# chamberbiasa.net
KiCad netlist of a schematic drawn in EAGLE
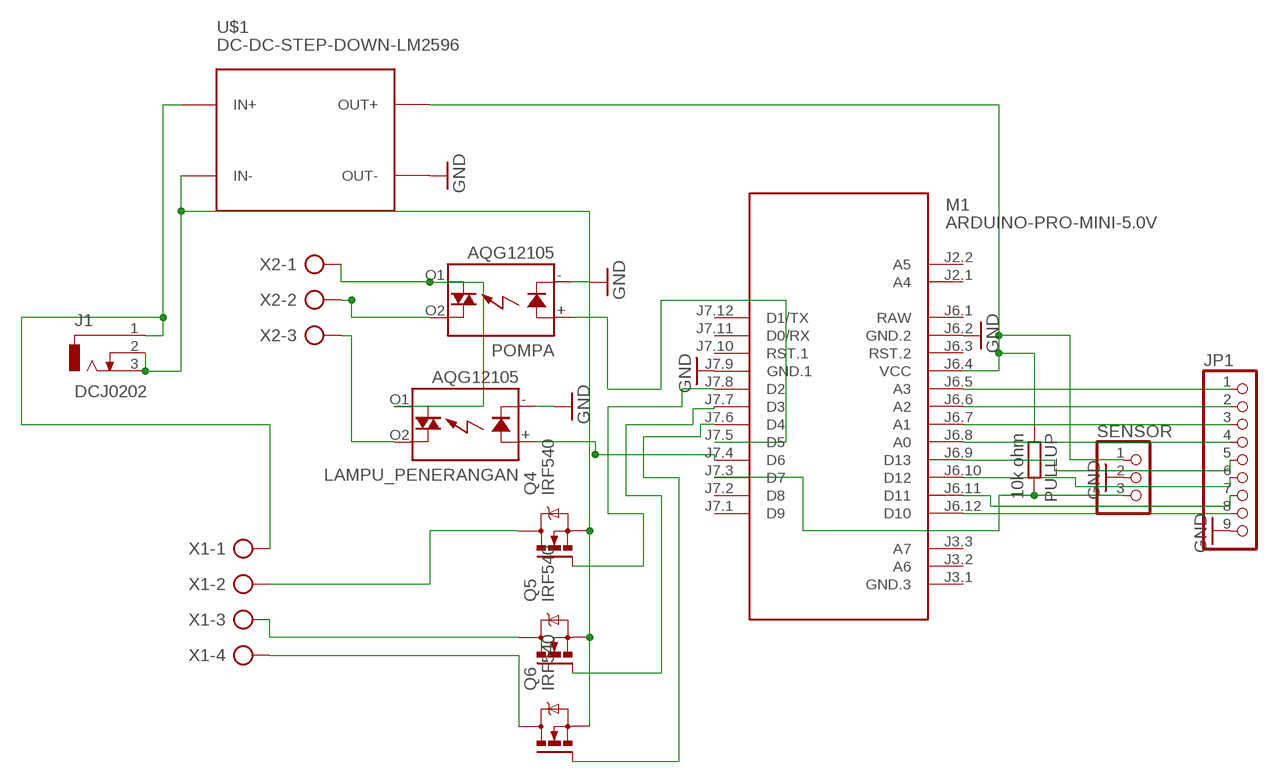
[diagram p0: schematic, sheet 1]

(export (version "E")
  (design (tool "Eeschema 10.0.6"))
  (components
    (comp (ref "J1")
      (value "DCJ0202")
      (footprint "eagle-import:DCJ0202")
      (libsource (lib "eagle-import") (part "DCJ0202"))
    )
    (comp (ref "JP1")
      (value "PINHD-1X9")
      (footprint "eagle-import:1X09")
      (libsource (lib "eagle-import") (part "PINHD-1X9"))
    )
    (comp (ref "LAMPU_PENERANGAN")
      (value "AQG12105")
      (footprint "eagle-import:AQG")
      (fields (field (name "MF") "AROMAT/ MATSUSHITA"))
      (libsource (lib "eagle-import") (part "AQG12105"))
    )
    (comp (ref "M1")
      (value "ARDUINO-PRO-MINI-5.0V")
      (footprint "eagle-import:ARDUINO-PRO-MINI")
      (libsource (lib "eagle-import") (part "ARDUINO-PRO-MINI-5.0V"))
    )
    (comp (ref "POMPA")
      (value "AQG12105")
      (footprint "eagle-import:AQG")
      (fields (field (name "MF") "AROMAT/ MATSUSHITA"))
      (libsource (lib "eagle-import") (part "AQG12105"))
    )
    (comp (ref "PULLUP")
      (value "10k ohm")
      (footprint "eagle-import:0204_7")
      (libsource (lib "eagle-import") (part "R-EU_0204/7"))
    )
    (comp (ref "Q4")
      (value "IRF540")
      (footprint "eagle-import:TO220BV")
      (libsource (lib "eagle-import") (part "IRF540"))
    )
    (comp (ref "Q5")
      (value "IRF540")
      (footprint "eagle-import:TO220BV")
      (libsource (lib "eagle-import") (part "IRF540"))
    )
    (comp (ref "Q6")
      (value "IRF540")
      (footprint "eagle-import:TO220BV")
      (libsource (lib "eagle-import") (part "IRF540"))
    )
    (comp (ref "SENSOR")
      (value "PINHD-1X3")
      (footprint "eagle-import:1X03")
      (libsource (lib "eagle-import") (part "PINHD-1X3"))
    )
    (comp (ref "U$1")
      (value "DC-DC-STEP-DOWN-LM2596")
      (footprint "eagle-import:DC-DC-STEP-DOWN-LM2596")
      (libsource (lib "eagle-import") (part "DC-DC-STEP-DOWN-LM2596"))
    )
    (comp (ref "X1")
      (value "AK300/4")
      (footprint "eagle-import:AK300_4")
      (libsource (lib "eagle-import") (part "AK300/4"))
    )
    (comp (ref "X2")
      (value "AK300/3")
      (footprint "eagle-import:AK300_3")
      (libsource (lib "eagle-import") (part "AK300/3"))
    )
  )
  (nets
    (net (code "1") (name "/RAW") (class "Default")
      (node (ref "M1") (pin "J6.1") (pinfunction "RAW_J6.1") (pintype "power_in"))
    )
    (net (code "2") (name "GND") (class "Default")
      (node (ref "JP1") (pin "9") (pinfunction "9_9") (pintype "passive"))
      (node (ref "LAMPU_PENERANGAN") (pin "-") (pinfunction "K_-") (pintype "passive"))
      (node (ref "M1") (pin "J6.2") (pinfunction "GND.2_J6.2") (pintype "power_in"))
      (node (ref "M1") (pin "J7.9") (pinfunction "GND.1_J7.9") (pintype "power_in"))
      (node (ref "POMPA") (pin "-") (pinfunction "K_-") (pintype "passive"))
      (node (ref "SENSOR") (pin "2") (pinfunction "2_2") (pintype "passive"))
      (node (ref "U$1") (pin "OUT-") (pinfunction "OUT-_OUT-") (pintype "bidirectional"))
    )
    (net (code "3") (name "Net-(J1-Pad2)") (class "Default")
      (node (ref "J1") (pin "2") (pinfunction "2_2") (pintype "passive"))
      (node (ref "J1") (pin "3") (pinfunction "3_3") (pintype "passive"))
      (node (ref "Q4") (pin "S") (pinfunction "S_S") (pintype "passive"))
      (node (ref "Q5") (pin "S") (pinfunction "S_S") (pintype "passive"))
      (node (ref "Q6") (pin "S") (pinfunction "S_S") (pintype "passive"))
      (node (ref "U$1") (pin "IN-") (pinfunction "IN-_IN-") (pintype "bidirectional"))
    )
    (net (code "4") (name "Net-(LAMPU_PENERANGAN-A)") (class "Default")
      (node (ref "LAMPU_PENERANGAN") (pin "+") (pinfunction "A_+") (pintype "passive"))
      (node (ref "M1") (pin "J7.4") (pinfunction "D6_J7.4") (pintype "bidirectional"))
    )
    (net (code "5") (name "Net-(LAMPU_PENERANGAN-DS1)") (class "Default")
      (node (ref "LAMPU_PENERANGAN") (pin "O2") (pinfunction "DS1_O2") (pintype "passive"))
      (node (ref "X2") (pin "3") (pinfunction "KL_3") (pintype "passive"))
    )
    (net (code "6") (name "Net-(LAMPU_PENERANGAN-DS2)") (class "Default")
      (node (ref "LAMPU_PENERANGAN") (pin "O1") (pinfunction "DS2_O1") (pintype "passive"))
      (node (ref "POMPA") (pin "O1") (pinfunction "DS2_O1") (pintype "passive"))
      (node (ref "X2") (pin "1") (pinfunction "KL_1") (pintype "passive"))
    )
    (net (code "7") (name "Net-(M1-A0)") (class "Default")
      (node (ref "JP1") (pin "4") (pinfunction "4_4") (pintype "passive"))
      (node (ref "M1") (pin "J6.8") (pinfunction "A0_J6.8") (pintype "bidirectional"))
    )
    (net (code "8") (name "Net-(M1-A1)") (class "Default")
      (node (ref "JP1") (pin "3") (pinfunction "3_3") (pintype "passive"))
      (node (ref "M1") (pin "J6.7") (pinfunction "A1_J6.7") (pintype "bidirectional"))
    )
    (net (code "9") (name "Net-(M1-A2)") (class "Default")
      (node (ref "JP1") (pin "2") (pinfunction "2_2") (pintype "passive"))
      (node (ref "M1") (pin "J6.6") (pinfunction "A2_J6.6") (pintype "bidirectional"))
    )
    (net (code "10") (name "Net-(M1-A3)") (class "Default")
      (node (ref "JP1") (pin "1") (pinfunction "1_1") (pintype "passive"))
      (node (ref "M1") (pin "J6.5") (pinfunction "A3_J6.5") (pintype "bidirectional"))
    )
    (net (code "11") (name "Net-(M1-D2)") (class "Default")
      (node (ref "M1") (pin "J7.8") (pinfunction "D2_J7.8") (pintype "bidirectional"))
      (node (ref "Q4") (pin "G") (pinfunction "G_G") (pintype "passive"))
    )
    (net (code "12") (name "Net-(M1-D3)") (class "Default")
      (node (ref "M1") (pin "J7.7") (pinfunction "D3_J7.7") (pintype "bidirectional"))
      (node (ref "Q5") (pin "G") (pinfunction "G_G") (pintype "passive"))
    )
    (net (code "13") (name "Net-(M1-D4)") (class "Default")
      (node (ref "M1") (pin "J7.6") (pinfunction "D4_J7.6") (pintype "bidirectional"))
      (node (ref "Q6") (pin "G") (pinfunction "G_G") (pintype "passive"))
    )
    (net (code "14") (name "Net-(M1-D5)") (class "Default")
      (node (ref "M1") (pin "J7.5") (pinfunction "D5_J7.5") (pintype "bidirectional"))
      (node (ref "POMPA") (pin "+") (pinfunction "A_+") (pintype "passive"))
    )
    (net (code "15") (name "Net-(M1-D7)") (class "Default")
      (node (ref "M1") (pin "J7.3") (pinfunction "D7_J7.3") (pintype "bidirectional"))
      (node (ref "PULLUP") (pin "2") (pinfunction "2_2") (pintype "passive"))
      (node (ref "SENSOR") (pin "3") (pinfunction "3_3") (pintype "passive"))
    )
    (net (code "16") (name "Net-(M1-D10)") (class "Default")
      (node (ref "JP1") (pin "8") (pinfunction "8_8") (pintype "passive"))
      (node (ref "M1") (pin "J6.12") (pinfunction "D10_J6.12") (pintype "bidirectional"))
    )
    (net (code "17") (name "Net-(M1-D11)") (class "Default")
      (node (ref "JP1") (pin "7") (pinfunction "7_7") (pintype "passive"))
      (node (ref "M1") (pin "J6.11") (pinfunction "D11_J6.11") (pintype "bidirectional"))
    )
    (net (code "18") (name "Net-(M1-D12)") (class "Default")
      (node (ref "JP1") (pin "6") (pinfunction "6_6") (pintype "passive"))
      (node (ref "M1") (pin "J6.10") (pinfunction "D12_J6.10") (pintype "bidirectional"))
    )
    (net (code "19") (name "Net-(M1-D13)") (class "Default")
      (node (ref "JP1") (pin "5") (pinfunction "5_5") (pintype "passive"))
      (node (ref "M1") (pin "J6.9") (pinfunction "D13_J6.9") (pintype "bidirectional"))
    )
    (net (code "20") (name "Net-(M1-VCC)") (class "Default")
      (node (ref "M1") (pin "J6.4") (pinfunction "VCC_J6.4") (pintype "power_in"))
      (node (ref "PULLUP") (pin "1") (pinfunction "1_1") (pintype "passive"))
      (node (ref "SENSOR") (pin "1") (pinfunction "1_1") (pintype "passive"))
      (node (ref "U$1") (pin "OUT+") (pinfunction "OUT+_OUT+") (pintype "bidirectional"))
    )
    (net (code "21") (name "Net-(POMPA-DS1)") (class "Default")
      (node (ref "POMPA") (pin "O2") (pinfunction "DS1_O2") (pintype "passive"))
      (node (ref "X2") (pin "2") (pinfunction "KL_2") (pintype "passive"))
    )
    (net (code "22") (name "Net-(X1A-KL)") (class "Default")
      (node (ref "J1") (pin "1") (pinfunction "1_1") (pintype "passive"))
      (node (ref "U$1") (pin "IN+") (pinfunction "IN+_IN+") (pintype "bidirectional"))
      (node (ref "X1") (pin "1") (pinfunction "KL_1") (pintype "passive"))
    )
    (net (code "23") (name "Net-(X1B-KL)") (class "Default")
      (node (ref "Q4") (pin "D") (pinfunction "D_D") (pintype "passive"))
      (node (ref "X1") (pin "2") (pinfunction "KL_2") (pintype "passive"))
    )
    (net (code "24") (name "Net-(X1C-KL)") (class "Default")
      (node (ref "Q5") (pin "D") (pinfunction "D_D") (pintype "passive"))
      (node (ref "X1") (pin "3") (pinfunction "KL_3") (pintype "passive"))
    )
    (net (code "25") (name "Net-(X1D-KL)") (class "Default")
      (node (ref "Q6") (pin "D") (pinfunction "D_D") (pintype "passive"))
      (node (ref "X1") (pin "4") (pinfunction "KL_4") (pintype "passive"))
    )
    (net (code "26") (name "unconnected-(M1-A4-PadJ2.1)") (class "Default")
      (node (ref "M1") (pin "J2.1") (pinfunction "A4_J2.1") (pintype "bidirectional"))
    )
    (net (code "27") (name "unconnected-(M1-A5-PadJ2.2)") (class "Default")
      (node (ref "M1") (pin "J2.2") (pinfunction "A5_J2.2") (pintype "bidirectional"))
    )
    (net (code "28") (name "unconnected-(M1-A6-PadJ3.2)") (class "Default")
      (node (ref "M1") (pin "J3.2") (pinfunction "A6_J3.2") (pintype "bidirectional"))
    )
    (net (code "29") (name "unconnected-(M1-A7-PadJ3.3)") (class "Default")
      (node (ref "M1") (pin "J3.3") (pinfunction "A7_J3.3") (pintype "bidirectional"))
    )
    (net (code "30") (name "unconnected-(M1-D0{slash}RX-PadJ7.11)") (class "Default")
      (node (ref "M1") (pin "J7.11") (pinfunction "D0/RX_J7.11") (pintype "bidirectional"))
    )
    (net (code "31") (name "unconnected-(M1-D1{slash}TX-PadJ7.12)") (class "Default")
      (node (ref "M1") (pin "J7.12") (pinfunction "D1/TX_J7.12") (pintype "bidirectional"))
    )
    (net (code "32") (name "unconnected-(M1-D8-PadJ7.2)") (class "Default")
      (node (ref "M1") (pin "J7.2") (pinfunction "D8_J7.2") (pintype "bidirectional"))
    )
    (net (code "33") (name "unconnected-(M1-D9-PadJ7.1)") (class "Default")
      (node (ref "M1") (pin "J7.1") (pinfunction "D9_J7.1") (pintype "bidirectional"))
    )
    (net (code "34") (name "unconnected-(M1-GND.3-PadJ3.1)") (class "Default")
      (node (ref "M1") (pin "J3.1") (pinfunction "GND.3_J3.1") (pintype "bidirectional"))
    )
    (net (code "35") (name "unconnected-(M1-RST.1-PadJ7.10)") (class "Default")
      (node (ref "M1") (pin "J7.10") (pinfunction "RST.1_J7.10") (pintype "bidirectional"))
    )
    (net (code "36") (name "unconnected-(M1-RST.2-PadJ6.3)") (class "Default")
      (node (ref "M1") (pin "J6.3") (pinfunction "RST.2_J6.3") (pintype "bidirectional"))
    )
  )
)
